# 24V_Main.net
KiCad netlist of a schematic drawn in Altium Designer
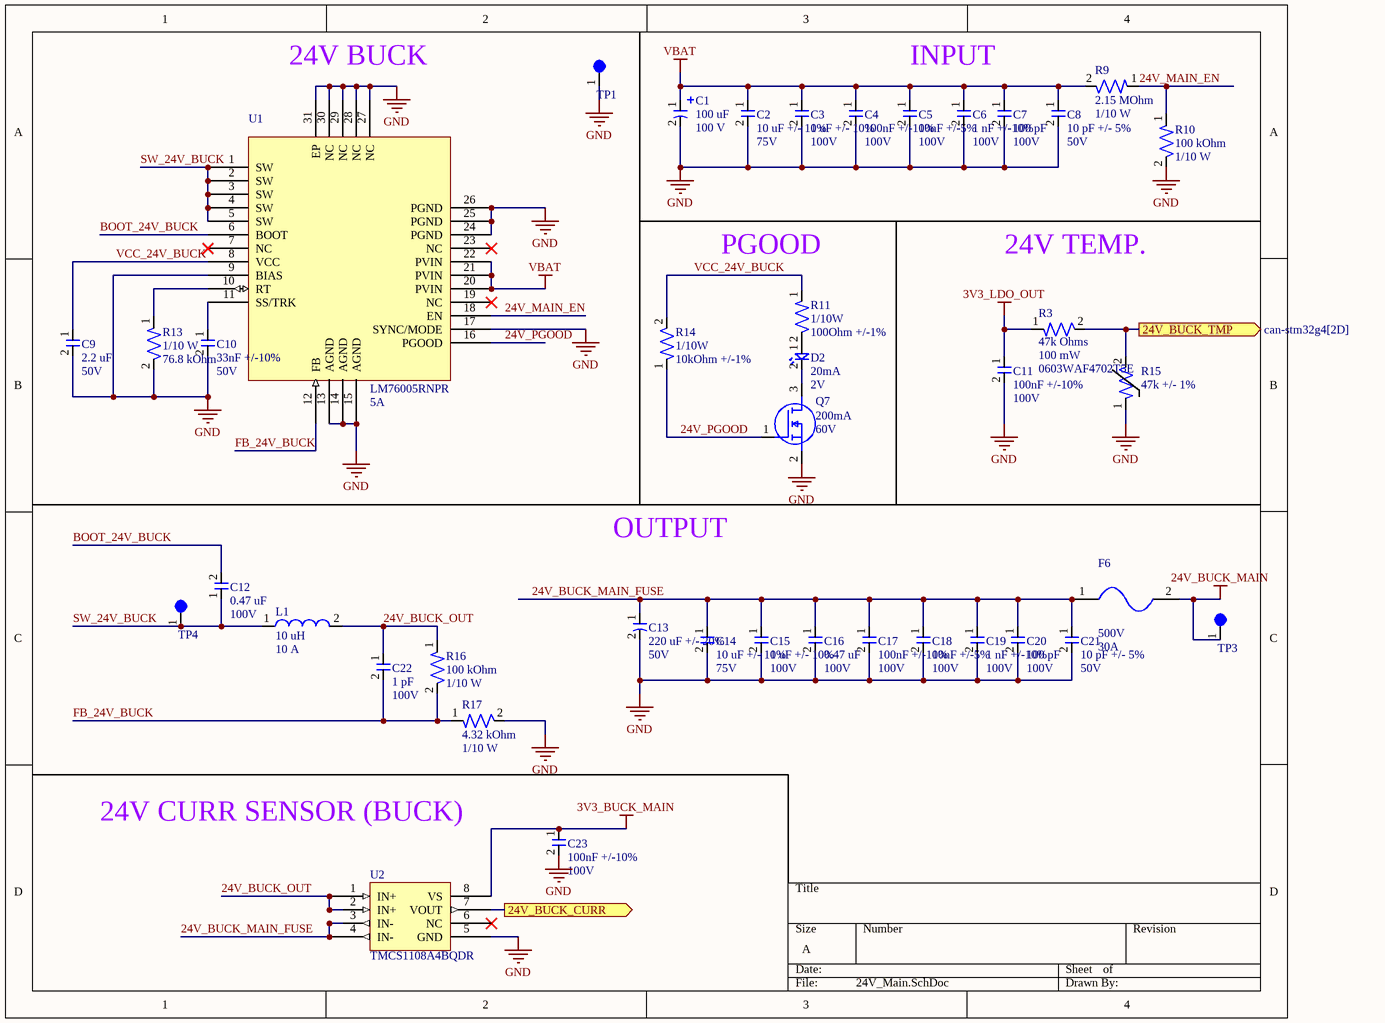
[diagram p0: 24V_Main.SchDoc]

(export (version "E")
  (design (tool "Eeschema 10.0.6"))
  (components
    (comp (ref "C1")
      (value "100SEV100M12.5X16")
      (footprint "ELEC-100U-0001")
      (description "100 µF 100 V Aluminum Electrolytic Capacitors Radial, Can - SMD 2000 Hrs @ 85°C")
      (fields
        (field (name "MANUFACTURER") "Rubycon")
        (field (name "TOLERANCE") "+/- 20%")
        (field (name "CAPACITANCE") "100 uF")
        (field (name "VOLTAGE") "100 V")
      )
      (libsource (lib "MasterLib") (part "ELEC-100U-0001"))
    )
    (comp (ref "C2")
      (value "C3225X7R1N106K250AC")
      (footprint "CAP-1210")
      (description "10 µF ±10% 75V Ceramic Capacitor X7R 1210 (3225 Metric)")
      (fields (field (name "CAPACITANCE") "10 uF +/- 10%") (field (name "VOLTAGE RATING") "75V"))
      (libsource (lib "MasterLib") (part "CAP-10U-0004"))
    )
    (comp (ref "C3")
      (value "CL31B105KCHNNNE")
      (footprint "CAP-1206 - duplicate")
      (description "1 µF ±10% 100V Ceramic Capacitor X7R 1206 (3216 Metric)")
      (fields (field (name "CAPACITANCE") "1 uF +/- 10%") (field (name "VOLTAGE") "100V"))
      (libsource (lib "MasterLib") (part "CAP-1U-0001"))
    )
    (comp (ref "C4")
      (value "CC0603KRX7R0BB104")
      (footprint "CAP-0603")
      (description "CAP CER 0.1UF 100V X7R 0603")
      (fields
        (field (name "MANUFACTURER") "YAGEO")
        (field (name "CAPACITANCE") "100nF +/-10%")
        (field (name "VOLTAGE RATING") "100V")
      )
      (libsource (lib "MasterLib") (part "CAP-100N-0001"))
    )
    (comp (ref "C5")
      (value "C1608C0G2A103J080AC")
      (footprint "CAP-0603")
      (description "CAP CER 10000PF 100V C0G 0603")
      (fields
        (field (name "MANUFACTURER") "TDK Corporation")
        (field (name "CAPACITANCE") "10nF +/-5%")
        (field (name "VOLTAGE RATING") "100V")
      )
      (libsource (lib "MasterLib") (part "CAP-10N-0002"))
    )
    (comp (ref "C6")
      (value "C0603Y102K1RAC7867")
      (footprint "CAP-0603")
      (description "1000 pF ±10% 100V Ceramic Capacitor X7R 0603 (1608 Metric)")
      (fields (field (name "CAPACITANCE") "1 nF +/-10%") (field (name "VOLTAGE") "100V"))
      (libsource (lib "MasterLib") (part "CAP-1N-0001"))
    )
    (comp (ref "C7")
      (value "0603N101J101CT")
      (footprint "CAP-0603")
      (description "100 pF ±5% 100V Ceramic Capacitor C0G, NP0 0603 (1608 Metric)")
      (fields
        (field (name "TOLERANCE") "+/-5%")
        (field (name "CAPACITANCE") "100 pF")
        (field (name "VOLTAGE") "100V")
      )
      (libsource (lib "MasterLib") (part "CAP-100P-0002"))
    )
    (comp (ref "C8")
      (value "0603N100J500CT")
      (footprint "CAP-0603")
      (description "10 pF ±5% 50V Ceramic Capacitor C0G, NP0 0603 (1608 Metric)")
      (fields
        (field (name "MANUFACTURER") "Walshin Technology Corporation")
        (field (name "CAPACITANCE") "10 pF +/- 5%")
        (field (name "VOLTAGE RATING") "50V")
      )
      (libsource (lib "MasterLib") (part "CAP-10P-0001"))
    )
    (comp (ref "C9")
      (value "UMK107BBJ225KA-T")
      (footprint "CAP-0603")
      (description "2.2 µF ±10% 50V Ceramic Capacitor X5R 0603 (1608 Metric)")
      (fields (field (name "CAPACITANCE") "2.2 uF") (field (name "OLTAGE") "50V"))
      (libsource (lib "MasterLib") (part "CAP-2.2U-0001"))
    )
    (comp (ref "C10")
      (value "CC0603KRX7R9BB333")
      (footprint "CAP-0603")
      (description "0.033 µF ±10% 50V Ceramic Capacitor X7R 0603 (1608 Metric)")
      (fields
        (field (name "MANUFACTURER") "YAGEO")
        (field (name "CAPACITANCE") "33nF +/-10%")
        (field (name "VOLTAGE RATING") "50V")
      )
      (libsource (lib "MasterLib") (part "CAP-33N-0001"))
    )
    (comp (ref "C11")
      (value "CC0603KRX7R0BB104")
      (footprint "CAP-0603")
      (description "CAP CER 0.1UF 100V X7R 0603")
      (fields
        (field (name "MANUFACTURER") "YAGEO")
        (field (name "CAPACITANCE") "100nF +/-10%")
        (field (name "VOLTAGE RATING") "100V")
      )
      (libsource (lib "MasterLib") (part "CAP-100N-0001"))
    )
    (comp (ref "C12")
      (value "KAM21KR72A474KL")
      (footprint "CAP-0805")
      (description "0.47 µF ±10% 100V Ceramic Capacitor X7R 0805 (2012 Metric)")
      (fields
        (field (name "TOLERANCE") "+/- 10%")
        (field (name "CAPACITANCE") "0.47 uF")
        (field (name "VOLTAGE") "100V")
      )
      (libsource (lib "MasterLib") (part "CAP-0.47U-0001"))
    )
    (comp (ref "C13")
      (value "50TZV220M10X10.5")
      (footprint "ELEC-220U-0003")
      (description "220 µF 50 V Aluminum Electrolytic Capacitors Radial, Can - SMD 2000 Hrs @ 105°C")
      (fields (field (name "CAPACITANCE") "220 uF +/- 20%") (field (name "VOLTAGE RATING") "50V"))
      (libsource (lib "MasterLib") (part "ELEC-220U-0003"))
    )
    (comp (ref "C14")
      (value "C3225X7R1N106K250AC")
      (footprint "CAP-1210")
      (description "10 µF ±10% 75V Ceramic Capacitor X7R 1210 (3225 Metric)")
      (fields (field (name "CAPACITANCE") "10 uF +/- 10%") (field (name "VOLTAGE RATING") "75V"))
      (libsource (lib "MasterLib") (part "CAP-10U-0004"))
    )
    (comp (ref "C15")
      (value "CL31B105KCHNNNE")
      (footprint "CAP-1206 - duplicate")
      (description "1 µF ±10% 100V Ceramic Capacitor X7R 1206 (3216 Metric)")
      (fields (field (name "CAPACITANCE") "1 uF +/- 10%") (field (name "VOLTAGE") "100V"))
      (libsource (lib "MasterLib") (part "CAP-1U-0001"))
    )
    (comp (ref "C16")
      (value "KAM21KR72A474KL")
      (footprint "CAP-0805")
      (description "0.47 µF ±10% 100V Ceramic Capacitor X7R 0805 (2012 Metric)")
      (fields
        (field (name "TOLERANCE") "+/- 10%")
        (field (name "CAPACITANCE") "0.47 uF")
        (field (name "VOLTAGE") "100V")
      )
      (libsource (lib "MasterLib") (part "CAP-0.47U-0001"))
    )
    (comp (ref "C17")
      (value "CC0603KRX7R0BB104")
      (footprint "CAP-0603")
      (description "CAP CER 0.1UF 100V X7R 0603")
      (fields
        (field (name "MANUFACTURER") "YAGEO")
        (field (name "CAPACITANCE") "100nF +/-10%")
        (field (name "VOLTAGE RATING") "100V")
      )
      (libsource (lib "MasterLib") (part "CAP-100N-0001"))
    )
    (comp (ref "C18")
      (value "C1608C0G2A103J080AC")
      (footprint "CAP-0603")
      (description "CAP CER 10000PF 100V C0G 0603")
      (fields
        (field (name "MANUFACTURER") "TDK Corporation")
        (field (name "CAPACITANCE") "10nF +/-5%")
        (field (name "VOLTAGE RATING") "100V")
      )
      (libsource (lib "MasterLib") (part "CAP-10N-0002"))
    )
    (comp (ref "C19")
      (value "C0603Y102K1RAC7867")
      (footprint "CAP-0603")
      (description "1000 pF ±10% 100V Ceramic Capacitor X7R 0603 (1608 Metric)")
      (fields (field (name "CAPACITANCE") "1 nF +/-10%") (field (name "VOLTAGE") "100V"))
      (libsource (lib "MasterLib") (part "CAP-1N-0001"))
    )
    (comp (ref "C20")
      (value "0603N101J101CT")
      (footprint "CAP-0603")
      (description "100 pF ±5% 100V Ceramic Capacitor C0G, NP0 0603 (1608 Metric)")
      (fields
        (field (name "TOLERANCE") "+/-5%")
        (field (name "CAPACITANCE") "100 pF")
        (field (name "VOLTAGE") "100V")
      )
      (libsource (lib "MasterLib") (part "CAP-100P-0002"))
    )
    (comp (ref "C21")
      (value "0603N100J500CT")
      (footprint "CAP-0603")
      (description "10 pF ±5% 50V Ceramic Capacitor C0G, NP0 0603 (1608 Metric)")
      (fields
        (field (name "MANUFACTURER") "Walshin Technology Corporation")
        (field (name "CAPACITANCE") "10 pF +/- 5%")
        (field (name "VOLTAGE RATING") "50V")
      )
      (libsource (lib "MasterLib") (part "CAP-10P-0001"))
    )
    (comp (ref "C22")
      (value "885012006087")
      (footprint "CAP-0603")
      (description "1 pF ±0.25pF 100V Ceramic Capacitor C0G, NP0 0603 (1608 Metric)")
      (fields
        (field (name "TOLERANCE") "+/- 0.25 pF")
        (field (name "CAPACITANCE") "1 pF")
        (field (name "VOLTAGE") "100V")
      )
      (libsource (lib "MasterLib") (part "CAP-1P-0001"))
    )
    (comp (ref "C23")
      (value "CC0603KRX7R0BB104")
      (footprint "CAP-0603")
      (description "CAP CER 0.1UF 100V X7R 0603")
      (fields
        (field (name "MANUFACTURER") "YAGEO")
        (field (name "CAPACITANCE") "100nF +/-10%")
        (field (name "VOLTAGE RATING") "100V")
      )
      (libsource (lib "MasterLib") (part "CAP-100N-0001"))
    )
    (comp (ref "D2")
      (value "150060AS75000")
      (footprint "LED-0603")
      (description "CAP CER 0.1UF 100V X7R 0603")
      (fields
        (field (name "MANUFACTURER") "Wurth Electronik")
        (field (name "CURRENT RATING") "20mA")
        (field (name "VF") "2V")
      )
      (libsource (lib "MasterLib") (part "LED_Amber_0001"))
    )
    (comp (ref "F6")
      (value "3568")
      (footprint "FUSE-ATM-0001")
      (description "Fuse Holder 30 A 500V 1 Circuit Blade Through Hole")
      (fields (field (name "VOLTAGE RATING") "500V") (field (name "CURRENT") "30A"))
      (libsource (lib "MasterLib") (part "FUSE-ATM-0001"))
    )
    (comp (ref "L1")
      (value "SRP1270-100M")
      (footprint "PWRIND-10U-0002")
      (description "10 µH Shielded Drum Core, Wirewound Inductor 10 A 16.8mOhm Max Nonstandard")
      (fields
        (field (name "TOLERANCE") "+/- 20%")
        (field (name "INDUCTANCE") "10 uH")
        (field (name "DCI") "10 A")
      )
      (libsource (lib "MasterLib") (part "PWRIND-10U-0002"))
    )
    (comp (ref "Q7")
      (value "T2N7002AK,LM")
      (footprint "NMOS-SOT23-3")
      (description "MOSFET N-CH 60V 200MA SOT23")
      (fields
        (field (name "MANUFACTURER") "Toshiba")
        (field (name "ID-CONTINUOUS") "200mA")
        (field (name "VDS-MAX") "60V")
      )
      (libsource (lib "MasterLib") (part "NMOS-200MA-0001"))
    )
    (comp (ref "R3")
      (value "0603WAF4702T5E")
      (footprint "RES-0603")
      (description "100mW Thick Film Resistors 75V ±100ppm/℃ ±1% 47kΩ 0603 Chip Resistor - Surface Mount ROHS")
      (fields (field (name "POWER") "100mW"))
      (libsource (lib "MasterLib") (part "RES-47k-0001-JLC"))
    )
    (comp (ref "R9")
      (value "RC0603FR-072M15L")
      (footprint "RES-0603")
      (description "2.15 MOhms ±1% 0.1W, 1/10W Chip Resistor 0603 (1608 Metric) Moisture Resistant Thick Film")
      (fields
        (field (name "TOLERANCE") "+/-1%")
        (field (name "RESISTANCE") "2.15 MOhm")
        (field (name "POWER") "1/10 W")
      )
      (libsource (lib "MasterLib") (part "RES-2.15M-0001"))
    )
    (comp (ref "R10")
      (value "RC0603FR-07100KL")
      (footprint "RES-0603")
      (description "100 kOhms ±1% 0.1W, 1/10W Chip Resistor 0603 (1608 Metric) Moisture Resistant Thick Film")
      (fields
        (field (name "TOLERANCE") "+/- 1%")
        (field (name "RESISTANCE") "100 kOhm")
        (field (name "POWER") "1/10 W")
      )
      (libsource (lib "MasterLib") (part "RES-100K-0003"))
    )
    (comp (ref "R11")
      (value "AC0603FR-10100RL")
      (footprint "RES-0603")
      (description "100 Ohms ±1% 0.1W, 1/10W Chip Resistor 0603 (1608 Metric) Automotive AEC-Q200 Thick Film")
      (fields
        (field (name "MANUFACTURER") "YAGEO")
        (field (name "POWER RATING") "1/10W")
        (field (name "RESISTANCE") "100Ohm +/-1%")
      )
      (libsource (lib "MasterLib") (part "RES-100-0002"))
    )
    (comp (ref "R13")
      (value "RC0603FR-0776K8L")
      (footprint "RES-0603")
      (description "76.8 kOhms ±1% 0.1W, 1/10W Chip Resistor 0603 (1608 Metric) Moisture Resistant Thick Film")
      (fields
        (field (name "MANUFACTURER") "Yageo")
        (field (name "TOLERANCE") "+/- 1%")
        (field (name "POWER") "1/10 W")
        (field (name "RESISTANCE") "76.8 kOhm")
      )
      (libsource (lib "MasterLib") (part "RES-76.8K-0001"))
    )
    (comp (ref "R14")
      (value "RC0603FR-0710KP")
      (footprint "RES-0603")
      (description "RES SMD 10K OHM 1% 1/10W 0603")
      (fields
        (field (name "MANUFACTURER") "YAGEO")
        (field (name "POWER RATING") "1/10W")
        (field (name "RESISTANCE") "10kOhm +/-1%")
      )
      (libsource (lib "MasterLib") (part "RES-10K-0002"))
    )
    (comp (ref "R15")
      (value "TMP6431DECR")
      (footprint "RES-0402")
      (description "PTC Thermistor 47 kOhms 0402 (1006 Metric)")
      (fields (field (name "MANUFACTURER") "Texas Instruments") (field (name "RESISTANCE") "47k +/- 1%"))
      (libsource (lib "MasterLib") (part "THERM-47K-0001"))
    )
    (comp (ref "R16")
      (value "RC0603FR-07100KL")
      (footprint "RES-0603")
      (description "100 kOhms ±1% 0.1W, 1/10W Chip Resistor 0603 (1608 Metric) Moisture Resistant Thick Film")
      (fields
        (field (name "TOLERANCE") "+/- 1%")
        (field (name "RESISTANCE") "100 kOhm")
        (field (name "POWER") "1/10 W")
      )
      (libsource (lib "MasterLib") (part "RES-100K-0003"))
    )
    (comp (ref "R17")
      (value "RC0603FR-074K32L")
      (footprint "RES-0603")
      (description "4.32 kOhms ±1% 0.1W, 1/10W Chip Resistor 0603 (1608 Metric) Moisture Resistant Thick Film")
      (fields
        (field (name "TOLERANCE") "+/-1%")
        (field (name "RESISTANCE") "4.32 kOhm")
        (field (name "POWER") "1/10 W")
      )
      (libsource (lib "MasterLib") (part "RES-4.32K-0001"))
    )
    (comp (ref "TP1")
      (value "5003")
      (footprint "TEST-POINT-0001")
      (description "Oranange PC Test Point, Miniature Phoisphor Bronze Silver Plating Through Hole Mounting Type")
      (libsource (lib "MasterLib") (part "TEST-POINT-0001"))
    )
    (comp (ref "TP3")
      (value "5003")
      (footprint "TEST-POINT-0001")
      (description "Oranange PC Test Point, Miniature Phoisphor Bronze Silver Plating Through Hole Mounting Type")
      (libsource (lib "MasterLib") (part "TEST-POINT-0001"))
    )
    (comp (ref "TP4")
      (value "5003")
      (footprint "TEST-POINT-0001")
      (description "Oranange PC Test Point, Miniature Phoisphor Bronze Silver Plating Through Hole Mounting Type")
      (libsource (lib "MasterLib") (part "TEST-POINT-0001"))
    )
    (comp (ref "U1")
      (value "LM76005RNPR")
      (footprint "IC-30-WQFN(6x4)")
      (description "Buck Switching Regulator IC Positive Adjustable 1V 1 Output 5A 30-WFQFN Exposed Pad")
      (fields (field (name "MANUFACTURER") "Texas Instruments") (field (name "CURRENT") "5A"))
      (libsource (lib "MasterLib") (part "IC-BUCK-0006"))
    )
    (comp (ref "U2")
      (value "TMCS1108A4BQDR")
      (footprint "IC-CURRENT-0001")
      (description "Current Sensor 1 Channel Hall Effect Bidirectional 8-SOIC (0.154\", 3.90mm Width)")
      (libsource (lib "MasterLib") (part "IC-CURRENT-0004"))
    )
  )
  (nets
    (net (code "1") (name "/24V_BUCK_CURR") (class "Default")
      (node (ref "U2") (pin "7") (pinfunction "VOUT_7") (pintype "output"))
    )
    (net (code "2") (name "/24V_BUCK_MAIN_FUSE") (class "Default")
      (node (ref "C13") (pin "1") (pinfunction "1_1") (pintype "passive"))
      (node (ref "C14") (pin "1") (pinfunction "1_1") (pintype "passive"))
      (node (ref "C15") (pin "1") (pinfunction "1_1") (pintype "passive"))
      (node (ref "C16") (pin "1") (pinfunction "1_1") (pintype "passive"))
      (node (ref "C17") (pin "1") (pinfunction "1_1") (pintype "passive"))
      (node (ref "C18") (pin "1") (pinfunction "1_1") (pintype "passive"))
      (node (ref "C19") (pin "1") (pinfunction "1_1") (pintype "passive"))
      (node (ref "C20") (pin "1") (pinfunction "1_1") (pintype "passive"))
      (node (ref "C21") (pin "1") (pinfunction "1_1") (pintype "passive"))
      (node (ref "F6") (pin "1") (pinfunction "0_1") (pintype "passive"))
      (node (ref "U2") (pin "3") (pinfunction "IN-_3") (pintype "output"))
      (node (ref "U2") (pin "4") (pinfunction "IN-_4") (pintype "output"))
    )
    (net (code "3") (name "/24V_BUCK_OUT") (class "Default")
      (node (ref "C22") (pin "1") (pinfunction "1_1") (pintype "passive"))
      (node (ref "L1") (pin "2") (pinfunction "2_2") (pintype "passive"))
      (node (ref "R16") (pin "1") (pinfunction "1_1") (pintype "passive"))
      (node (ref "U2") (pin "1") (pinfunction "IN+_1") (pintype "input"))
      (node (ref "U2") (pin "2") (pinfunction "IN+_2") (pintype "input"))
    )
    (net (code "4") (name "/24V_BUCK_TMP") (class "Default")
      (node (ref "R15") (pin "2") (pinfunction "2_2") (pintype "passive"))
      (node (ref "R3") (pin "2") (pinfunction "2_2") (pintype "passive"))
    )
    (net (code "5") (name "/24V_MAIN_EN") (class "Default")
      (node (ref "R10") (pin "1") (pinfunction "1_1") (pintype "passive"))
      (node (ref "R9") (pin "1") (pinfunction "1_1") (pintype "passive"))
      (node (ref "U1") (pin "18") (pinfunction "EN_18") (pintype "power_in"))
    )
    (net (code "6") (name "/24V_PGOOD") (class "Default")
      (node (ref "Q7") (pin "1") (pinfunction "G_1") (pintype "passive"))
      (node (ref "R14") (pin "1") (pinfunction "1_1") (pintype "passive"))
      (node (ref "U1") (pin "16") (pinfunction "PGOOD_16") (pintype "power_in"))
    )
    (net (code "8") (name "/BOOT_24V_BUCK") (class "Default")
      (node (ref "C12") (pin "2") (pinfunction "2_2") (pintype "passive"))
      (node (ref "U1") (pin "6") (pinfunction "BOOT_6") (pintype "power_in"))
    )
    (net (code "9") (name "/FB_24V_BUCK") (class "Default")
      (node (ref "C22") (pin "2") (pinfunction "2_2") (pintype "passive"))
      (node (ref "R16") (pin "2") (pinfunction "2_2") (pintype "passive"))
      (node (ref "R17") (pin "1") (pinfunction "1_1") (pintype "passive"))
      (node (ref "U1") (pin "12") (pinfunction "FB_12") (pintype "input"))
    )
    (net (code "10") (name "/SW_24V_BUCK") (class "Default")
      (node (ref "C12") (pin "1") (pinfunction "1_1") (pintype "passive"))
      (node (ref "L1") (pin "1") (pinfunction "1_1") (pintype "passive"))
      (node (ref "TP4") (pin "1") (pinfunction "0_1") (pintype "passive"))
      (node (ref "U1") (pin "1") (pinfunction "SW_1") (pintype "power_in"))
      (node (ref "U1") (pin "2") (pinfunction "SW_2") (pintype "power_in"))
      (node (ref "U1") (pin "3") (pinfunction "SW_3") (pintype "power_in"))
      (node (ref "U1") (pin "4") (pinfunction "SW_4") (pintype "power_in"))
      (node (ref "U1") (pin "5") (pinfunction "SW_5") (pintype "power_in"))
    )
    (net (code "11") (name "/VCC_24V_BUCK") (class "Default")
      (node (ref "C9") (pin "1") (pinfunction "1_1") (pintype "passive"))
      (node (ref "R11") (pin "1") (pinfunction "1_1") (pintype "passive"))
      (node (ref "R14") (pin "2") (pinfunction "2_2") (pintype "passive"))
      (node (ref "U1") (pin "8") (pinfunction "VCC_8") (pintype "power_in"))
    )
    (net (code "12") (name "3V3_BUCK_MAIN") (class "Default")
      (node (ref "C23") (pin "1") (pinfunction "1_1") (pintype "passive"))
      (node (ref "U2") (pin "8") (pinfunction "VS_8") (pintype "power_in"))
    )
    (net (code "13") (name "3V3_LDO_OUT") (class "Default")
      (node (ref "C11") (pin "1") (pinfunction "1_1") (pintype "passive"))
      (node (ref "R3") (pin "1") (pinfunction "1_1") (pintype "passive"))
    )
    (net (code "14") (name "24V_BUCK_MAIN") (class "Default")
      (node (ref "F6") (pin "2") (pinfunction "1_2") (pintype "passive"))
      (node (ref "TP3") (pin "1") (pinfunction "0_1") (pintype "passive"))
    )
    (net (code "15") (name "GND") (class "Default")
      (node (ref "C1") (pin "2") (pinfunction "2_2") (pintype "passive"))
      (node (ref "C10") (pin "2") (pinfunction "2_2") (pintype "passive"))
      (node (ref "C11") (pin "2") (pinfunction "2_2") (pintype "passive"))
      (node (ref "C13") (pin "2") (pinfunction "2_2") (pintype "passive"))
      (node (ref "C14") (pin "2") (pinfunction "2_2") (pintype "passive"))
      (node (ref "C15") (pin "2") (pinfunction "2_2") (pintype "passive"))
      (node (ref "C16") (pin "2") (pinfunction "2_2") (pintype "passive"))
      (node (ref "C17") (pin "2") (pinfunction "2_2") (pintype "passive"))
      (node (ref "C18") (pin "2") (pinfunction "2_2") (pintype "passive"))
      (node (ref "C19") (pin "2") (pinfunction "2_2") (pintype "passive"))
      (node (ref "C2") (pin "2") (pinfunction "2_2") (pintype "passive"))
      (node (ref "C20") (pin "2") (pinfunction "2_2") (pintype "passive"))
      (node (ref "C21") (pin "2") (pinfunction "2_2") (pintype "passive"))
      (node (ref "C23") (pin "2") (pinfunction "2_2") (pintype "passive"))
      (node (ref "C3") (pin "2") (pinfunction "2_2") (pintype "passive"))
      (node (ref "C4") (pin "2") (pinfunction "2_2") (pintype "passive"))
      (node (ref "C5") (pin "2") (pinfunction "2_2") (pintype "passive"))
      (node (ref "C6") (pin "2") (pinfunction "2_2") (pintype "passive"))
      (node (ref "C7") (pin "2") (pinfunction "2_2") (pintype "passive"))
      (node (ref "C8") (pin "2") (pinfunction "2_2") (pintype "passive"))
      (node (ref "C9") (pin "2") (pinfunction "2_2") (pintype "passive"))
      (node (ref "Q7") (pin "2") (pinfunction "S_2") (pintype "passive"))
      (node (ref "R10") (pin "2") (pinfunction "2_2") (pintype "passive"))
      (node (ref "R13") (pin "2") (pinfunction "2_2") (pintype "passive"))
      (node (ref "R15") (pin "1") (pinfunction "1_1") (pintype "passive"))
      (node (ref "R17") (pin "2") (pinfunction "2_2") (pintype "passive"))
      (node (ref "TP1") (pin "1") (pinfunction "0_1") (pintype "passive"))
      (node (ref "U1") (pin "13") (pinfunction "AGND_13") (pintype "power_in"))
      (node (ref "U1") (pin "14") (pinfunction "AGND_14") (pintype "power_in"))
      (node (ref "U1") (pin "15") (pinfunction "AGND_15") (pintype "power_in"))
      (node (ref "U1") (pin "17") (pinfunction "SYNC/MODE_17") (pintype "power_in"))
      (node (ref "U1") (pin "24") (pinfunction "PGND_24") (pintype "power_in"))
      (node (ref "U1") (pin "25") (pinfunction "PGND_25") (pintype "power_in"))
      (node (ref "U1") (pin "26") (pinfunction "PGND_26") (pintype "power_in"))
      (node (ref "U1") (pin "27") (pinfunction "NC_27") (pintype "power_in"))
      (node (ref "U1") (pin "28") (pinfunction "NC_28") (pintype "power_in"))
      (node (ref "U1") (pin "29") (pinfunction "NC_29") (pintype "power_in"))
      (node (ref "U1") (pin "30") (pinfunction "NC_30") (pintype "power_in"))
      (node (ref "U1") (pin "31") (pinfunction "EP_31") (pintype "power_in"))
      (node (ref "U1") (pin "9") (pinfunction "BIAS_9") (pintype "power_in"))
      (node (ref "U2") (pin "5") (pinfunction "GND_5") (pintype "power_in"))
    )
    (net (code "16") (name "Net-(D2-Pad1)") (class "Default")
      (node (ref "D2") (pin "1") (pinfunction "1_1") (pintype "passive"))
      (node (ref "R11") (pin "2") (pinfunction "2_2") (pintype "passive"))
    )
    (net (code "17") (name "Net-(Q7-D)") (class "Default")
      (node (ref "D2") (pin "2") (pinfunction "2_2") (pintype "passive"))
      (node (ref "Q7") (pin "3") (pinfunction "D_3") (pintype "passive"))
    )
    (net (code "18") (name "Net-(U1-RT)") (class "Default")
      (node (ref "R13") (pin "1") (pinfunction "1_1") (pintype "passive"))
      (node (ref "U1") (pin "10") (pinfunction "RT_10") (pintype "bidirectional"))
    )
    (net (code "19") (name "Net-(U1-SS{slash}TRK)") (class "Default")
      (node (ref "C10") (pin "1") (pinfunction "1_1") (pintype "passive"))
      (node (ref "U1") (pin "11") (pinfunction "SS/TRK_11") (pintype "passive"))
    )
    (net (code "20") (name "VBAT") (class "Default")
      (node (ref "C1") (pin "1") (pinfunction "1_1") (pintype "passive"))
      (node (ref "C2") (pin "1") (pinfunction "1_1") (pintype "passive"))
      (node (ref "C3") (pin "1") (pinfunction "1_1") (pintype "passive"))
      (node (ref "C4") (pin "1") (pinfunction "1_1") (pintype "passive"))
      (node (ref "C5") (pin "1") (pinfunction "1_1") (pintype "passive"))
      (node (ref "C6") (pin "1") (pinfunction "1_1") (pintype "passive"))
      (node (ref "C7") (pin "1") (pinfunction "1_1") (pintype "passive"))
      (node (ref "C8") (pin "1") (pinfunction "1_1") (pintype "passive"))
      (node (ref "R9") (pin "2") (pinfunction "2_2") (pintype "passive"))
      (node (ref "U1") (pin "20") (pinfunction "PVIN_20") (pintype "power_in"))
      (node (ref "U1") (pin "21") (pinfunction "PVIN_21") (pintype "power_in"))
      (node (ref "U1") (pin "22") (pinfunction "PVIN_22") (pintype "power_in"))
    )
    (net (code "21") (name "unconnected-(U1-NC-Pad7)") (class "Default")
      (node (ref "U1") (pin "7") (pinfunction "NC_7") (pintype "power_in+no_connect"))
    )
    (net (code "22") (name "unconnected-(U1-NC-Pad19)") (class "Default")
      (node (ref "U1") (pin "19") (pinfunction "NC_19") (pintype "power_in+no_connect"))
    )
    (net (code "23") (name "unconnected-(U1-NC-Pad23)") (class "Default")
      (node (ref "U1") (pin "23") (pinfunction "NC_23") (pintype "tri_state+no_connect"))
    )
    (net (code "24") (name "unconnected-(U2-NC-Pad6)") (class "Default")
      (node (ref "U2") (pin "6") (pinfunction "NC_6") (pintype "tri_state+no_connect"))
    )
  )
)
